# 04_-_Storage.net
KiCad netlist of a schematic drawn in Altium Designer
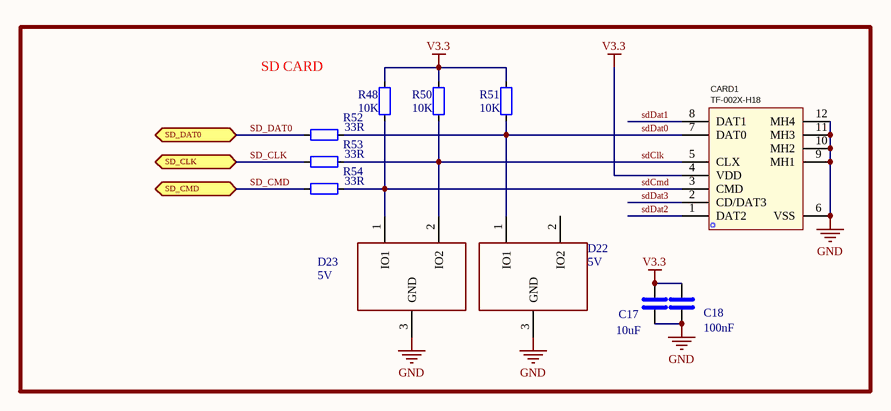
[diagram p0: 04 - Storage.SchDoc]

(export (version "E")
  (design (tool "Eeschema 10.0.6"))
  (components
    (comp (ref "C17")
      (value "10uF")
      (footprint "CAP_0805")
      (fields (field (name "LCSC PART") "C1713"))
      (libsource (lib "WalterFeels") (part "C"))
    )
    (comp (ref "C18")
      (value "100nF")
      (footprint "CAP_0603")
      (fields (field (name "LCSC PART") "C6119867"))
      (libsource (lib "WalterFeels") (part "C"))
    )
    (comp (ref "CARD1")
      (value "TF-002X-H18")
      (footprint "SIM-SMD_TF-002-H18")
      (description "Card Slot MicroSD card (TF card) Flip type SMD SD Card / Memory Card Connector ROHS")
      (fields (field (name "MANUFACTURER") "SOFNG(硕方)") (field (name "LCSC PART") "C125814"))
      (libsource (lib "WalterFeels") (part "TF-002X-H18"))
    )
    (comp (ref "D22")
      (value "5V")
      (footprint "TPD2E2U06DCKR")
      (fields
        (field (name "LCSC PART") "C5310938")
        (field (name "Comment") "Q100 TO CATALOG SPIN OF TPD2E2U0")
      )
      (libsource (lib "MIKRODEV_LIBRARY") (part "Q100 TO CATALOG SPIN OF TPD2E2U0"))
    )
    (comp (ref "D23")
      (value "5V")
      (footprint "TPD2E2U06DCKR")
      (fields
        (field (name "LCSC PART") "C5310938")
        (field (name "Comment") "Q100 TO CATALOG SPIN OF TPD2E2U0")
      )
      (libsource (lib "MIKRODEV_LIBRARY") (part "Q100 TO CATALOG SPIN OF TPD2E2U0"))
    )
    (comp (ref "R48")
      (value "10K")
      (footprint "RES_0603")
      (fields (field (name "LCSC PART") "C25804") (field (name "Comment") "10K 1%"))
      (libsource (lib "Device") (part "R"))
    )
    (comp (ref "R50")
      (value "10K")
      (footprint "RES_0603")
      (fields (field (name "LCSC PART") "C25804") (field (name "Comment") "10K 1%"))
      (libsource (lib "Device") (part "R"))
    )
    (comp (ref "R51")
      (value "10K")
      (footprint "RES_0603")
      (fields (field (name "LCSC PART") "C25804") (field (name "Comment") "10K 1%"))
      (libsource (lib "Device") (part "R"))
    )
    (comp (ref "R52")
      (value "33R")
      (footprint "RES_0603")
      (description "100mW Thick Film Resistors 75V ±100ppm/℃ ±1% 33Ω 0603 Chip Resistor - Surface Mount ROHS")
      (fields (field (name "LCSC PART") "C23140"))
      (libsource (lib "") (part "R_1"))
    )
    (comp (ref "R53")
      (value "33R")
      (footprint "RES_0603")
      (description "100mW Thick Film Resistors 75V ±100ppm/℃ ±1% 33Ω 0603 Chip Resistor - Surface Mount ROHS")
      (fields (field (name "LCSC PART") "C23140"))
      (libsource (lib "") (part "R_1"))
    )
    (comp (ref "R54")
      (value "33R")
      (footprint "RES_0603")
      (description "100mW Thick Film Resistors 75V ±100ppm/℃ ±1% 33Ω 0603 Chip Resistor - Surface Mount ROHS")
      (fields (field (name "LCSC PART") "C23140"))
      (libsource (lib "") (part "R_1"))
    )
  )
  (nets
    (net (code "1") (name "/SD_CLK") (class "Default")
      (node (ref "R53") (pin "1") (pinfunction "1_1") (pintype "passive"))
    )
    (net (code "2") (name "/SD_CMD") (class "Default")
      (node (ref "R54") (pin "1") (pinfunction "1_1") (pintype "passive"))
    )
    (net (code "3") (name "/SD_DAT0") (class "Default")
      (node (ref "R52") (pin "1") (pinfunction "1_1") (pintype "passive"))
    )
    (net (code "4") (name "/sdClk") (class "Default")
      (node (ref "CARD1") (pin "5") (pinfunction "CLX_5") (pintype "passive"))
      (node (ref "D23") (pin "2") (pinfunction "IO2_2") (pintype "passive"))
      (node (ref "R50") (pin "2") (pinfunction "2_2") (pintype "passive"))
      (node (ref "R53") (pin "2") (pinfunction "2_2") (pintype "passive"))
    )
    (net (code "5") (name "/sdCmd") (class "Default")
      (node (ref "CARD1") (pin "3") (pinfunction "CMD_3") (pintype "passive"))
      (node (ref "D23") (pin "1") (pinfunction "IO1_1") (pintype "passive"))
      (node (ref "R48") (pin "2") (pinfunction "2_2") (pintype "passive"))
      (node (ref "R54") (pin "2") (pinfunction "2_2") (pintype "passive"))
    )
    (net (code "6") (name "/sdDat0") (class "Default")
      (node (ref "CARD1") (pin "7") (pinfunction "DAT0_7") (pintype "passive"))
      (node (ref "D22") (pin "1") (pinfunction "IO1_1") (pintype "passive"))
      (node (ref "R51") (pin "2") (pinfunction "2_2") (pintype "passive"))
      (node (ref "R52") (pin "2") (pinfunction "2_2") (pintype "passive"))
    )
    (net (code "7") (name "/sdDat1") (class "Default")
      (node (ref "CARD1") (pin "8") (pinfunction "DAT1_8") (pintype "passive"))
    )
    (net (code "8") (name "/sdDat2") (class "Default")
      (node (ref "CARD1") (pin "1") (pinfunction "DAT2_1") (pintype "passive"))
    )
    (net (code "9") (name "/sdDat3") (class "Default")
      (node (ref "CARD1") (pin "2") (pinfunction "CD/DAT3_2") (pintype "passive"))
    )
    (net (code "10") (name "GND") (class "Default")
      (node (ref "C17") (pin "2") (pinfunction "2_2") (pintype "passive"))
      (node (ref "C18") (pin "2") (pinfunction "2_2") (pintype "passive"))
      (node (ref "CARD1") (pin "10") (pinfunction "MH2_10") (pintype "passive"))
      (node (ref "CARD1") (pin "11") (pinfunction "MH3_11") (pintype "passive"))
      (node (ref "CARD1") (pin "12") (pinfunction "MH4_12") (pintype "passive"))
      (node (ref "CARD1") (pin "6") (pinfunction "VSS_6") (pintype "passive"))
      (node (ref "CARD1") (pin "9") (pinfunction "MH1_9") (pintype "passive"))
      (node (ref "D22") (pin "3") (pinfunction "GND_3") (pintype "passive"))
      (node (ref "D23") (pin "3") (pinfunction "GND_3") (pintype "passive"))
    )
    (net (code "11") (name "V3.3") (class "Default")
      (node (ref "C17") (pin "1") (pinfunction "1_1") (pintype "passive"))
      (node (ref "C18") (pin "1") (pinfunction "1_1") (pintype "passive"))
      (node (ref "CARD1") (pin "4") (pinfunction "VDD_4") (pintype "passive"))
      (node (ref "R48") (pin "1") (pinfunction "1_1") (pintype "passive"))
      (node (ref "R50") (pin "1") (pinfunction "1_1") (pintype "passive"))
      (node (ref "R51") (pin "1") (pinfunction "1_1") (pintype "passive"))
    )
    (net (code "12") (name "unconnected-(D22-IO2-Pad2)") (class "Default")
      (node (ref "D22") (pin "2") (pinfunction "IO2_2") (pintype "passive"))
    )
  )
)
